# Converter.net
KiCad netlist of a schematic drawn in Altium Designer
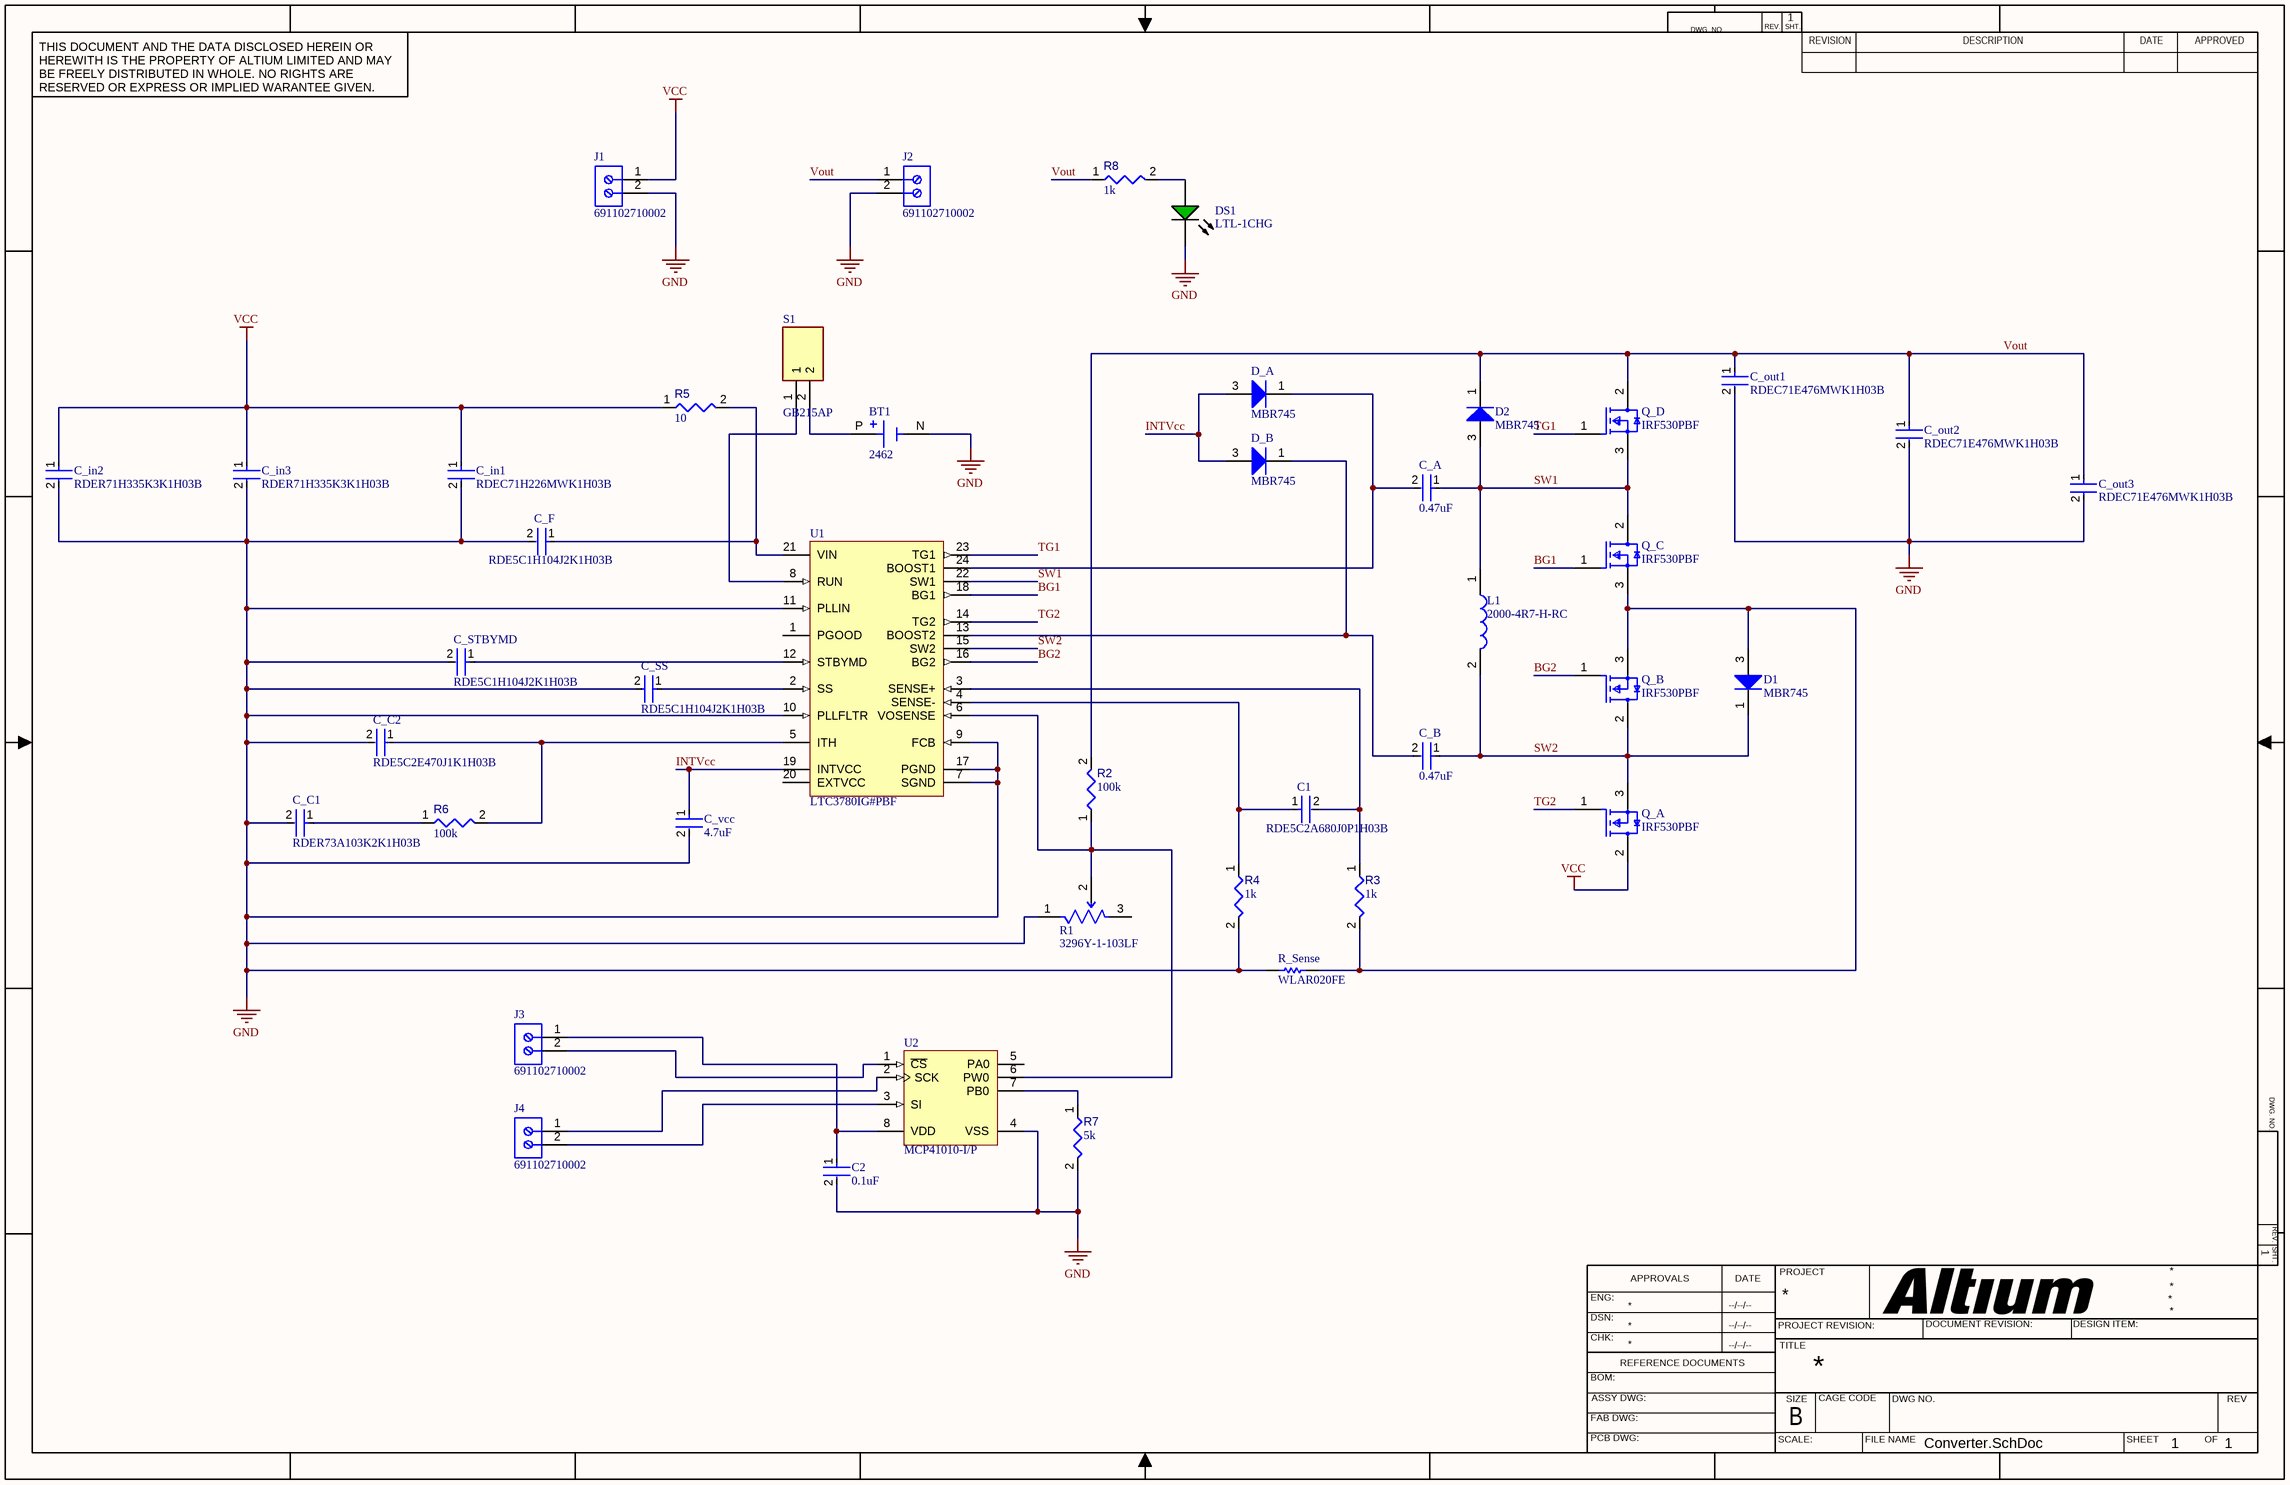
[diagram p0:  Converter.SchDoc]

(export (version "E")
  (design (tool "Eeschema 10.0.6"))
  (components
    (comp (ref "BT1")
      (value "2462")
      (footprint "2462:BAT_2462")
      (description "Battery Holder (Open) AA 2 Cell PC Pin")
      (fields (field (name "MF") "{'manufacturer': u'Keystone'}"))
      (libsource (lib "*") (part "2462"))
    )
    (comp (ref "C1")
      (value "RDE5C2A680J0P1H03B")
      (footprint "FP-RDE0P1-MFG")
      (description "Ceramic Capacitor 68pF ±5% 100V C0G Radial")
      (fields (field (name "TOLERANCE") "5%"))
      (libsource (lib "Altium Content Vault") (part "b4654b650e69147ec39a6b967a45e02"))
    )
    (comp (ref "C2")
      (value "0.1uF")
      (footprint "FP-RDE2M1-MFG")
      (description "Ceramic Capacitor 4.7uF ±10% 50V X7S Radial")
      (fields (field (name "TOLERANCE") "10%"))
      (libsource (lib "Altium Content Vault") (part "b4654b650e69147ec39a6b967a45e02"))
    )
    (comp (ref "C_A")
      (value "0.47uF")
      (footprint "FP-RCE1A2-MFG")
      (description "Cap Ceramic 470nF 50V X7R ±10% Radial 2.5mm +125°C Automotive Bulk")
      (fields (field (name "TOLERANCE") "10%"))
      (libsource (lib "Altium Content Vault") (part "02cd4be3c70576c341d710602a673aa"))
    )
    (comp (ref "C_B")
      (value "0.47uF")
      (footprint "FP-RCE1A2-MFG")
      (description "Cap Ceramic 470nF 50V X7R ±10% Radial 2.5mm +125°C Automotive Bulk")
      (fields (field (name "TOLERANCE") "10%"))
      (libsource (lib "Altium Content Vault") (part "02cd4be3c70576c341d710602a673aa"))
    )
    (comp (ref "C_C1")
      (value "RDER73A103K2K1H03B")
      (footprint "FP-RDE2M1-MFG")
      (description "Ceramic Capacitor 10nF ±10% 1kV X7R Radial")
      (fields (field (name "TOLERANCE") "10%"))
      (libsource (lib "Altium Content Vault") (part "b4654b650e69147ec39a6b967a45e02"))
    )
    (comp (ref "C_C2")
      (value "RDE5C2E470J1K1H03B")
      (footprint "FP-RDE1K1-MFG")
      (description "Ceramic Capacitor 47pF ±5% 250V C0G Radial")
      (libsource (lib "Altium Content Vault") (part "02cd4be3c70576c341d710602a673aa"))
    )
    (comp (ref "C_F")
      (value "RDE5C1H104J2K1H03B")
      (footprint "FP-RDE2M1-MFG")
      (description "Ceramic Capacitor 100nF ±5% 50V C0G Radial")
      (libsource (lib "Altium Content Vault") (part "b4654b650e69147ec39a6b967a45e02"))
    )
    (comp (ref "C_in1")
      (value "RDEC71H226MWK1H03B")
      (footprint "FP-RDEWK1-MFG")
      (description "CAP CER 22UF 50V X7S RADIAL")
      (fields (field (name "TOLERANCE") "20%"))
      (libsource (lib "Altium Content Vault") (part "02cd4be3c70576c341d710602a673aa"))
    )
    (comp (ref "C_in2")
      (value "RDER71H335K3K1H03B")
      (footprint "FP-RDE3M1-MFG")
      (description "Ceramic Capacitor 3.3uF ±10% 50V X7R Radial")
      (fields (field (name "TOLERANCE") "10%"))
      (libsource (lib "Altium Content Vault") (part "b4654b650e69147ec39a6b967a45e02"))
    )
    (comp (ref "C_in3")
      (value "RDER71H335K3K1H03B")
      (footprint "FP-RDE3M1-MFG")
      (description "Ceramic Capacitor 3.3uF ±10% 50V X7R Radial")
      (fields (field (name "TOLERANCE") "10%"))
      (libsource (lib "Altium Content Vault") (part "b4654b650e69147ec39a6b967a45e02"))
    )
    (comp (ref "C_out1")
      (value "RDEC71E476MWK1H03B")
      (footprint "FP-RDEWK1-MFG")
      (description "Ceramic Capacitor 47uF ±20% 25V X7S Radial")
      (fields (field (name "TOLERANCE") "20%"))
      (libsource (lib "Altium Content Vault") (part "02cd4be3c70576c341d710602a673aa"))
    )
    (comp (ref "C_out2")
      (value "RDEC71E476MWK1H03B")
      (footprint "FP-RDEWK1-MFG")
      (description "Ceramic Capacitor 47uF ±20% 25V X7S Radial")
      (fields (field (name "TOLERANCE") "20%"))
      (libsource (lib "Altium Content Vault") (part "02cd4be3c70576c341d710602a673aa"))
    )
    (comp (ref "C_out3")
      (value "RDEC71E476MWK1H03B")
      (footprint "FP-RDEWK1-MFG")
      (description "Ceramic Capacitor 47uF ±20% 25V X7S Radial")
      (fields (field (name "TOLERANCE") "20%"))
      (libsource (lib "Altium Content Vault") (part "02cd4be3c70576c341d710602a673aa"))
    )
    (comp (ref "C_SS")
      (value "RDE5C1H104J2K1H03B")
      (footprint "FP-RDE2M1-MFG")
      (description "Ceramic Capacitor 100nF ±5% 50V C0G Radial")
      (libsource (lib "Altium Content Vault") (part "b4654b650e69147ec39a6b967a45e02"))
    )
    (comp (ref "C_STBYMD")
      (value "RDE5C1H104J2K1H03B")
      (footprint "FP-RDE2M1-MFG")
      (description "Ceramic Capacitor 100nF ±5% 50V C0G Radial")
      (libsource (lib "Altium Content Vault") (part "b4654b650e69147ec39a6b967a45e02"))
    )
    (comp (ref "C_vcc")
      (value "4.7uF")
      (footprint "FP-RDE2M1-MFG")
      (description "Ceramic Capacitor 4.7uF ±10% 50V X7S Radial")
      (fields (field (name "TOLERANCE") "10%"))
      (libsource (lib "Altium Content Vault") (part "b4654b650e69147ec39a6b967a45e02"))
    )
    (comp (ref "D1")
      (value "MBR745")
      (footprint "ONSC-TO-220-2-221B-04_E")
      (description "SWITCHMODE(TM) Power Rectifier, 2-Pin TO-220, Tube")
      (fields (field (name "MANUFACTURER") "On Semiconductor"))
      (libsource (lib "Altium Content Vault") (part "ONSC-D-K1A3-2_A"))
    )
    (comp (ref "D2")
      (value "MBR745")
      (footprint "ONSC-TO-220-2-221B-04_E")
      (description "SWITCHMODE(TM) Power Rectifier, 2-Pin TO-220, Tube")
      (fields (field (name "MANUFACTURER") "On Semiconductor"))
      (libsource (lib "Altium Content Vault") (part "ONSC-D-K1A3-2_A"))
    )
    (comp (ref "DS1")
      (value "LTL-1CHG")
      (footprint "LTST-LTL-1CHG-2")
      (description "LED Uni-Color Green, 100 mW, 30 mA, -55 to 100 degC, 2-Pin THD, RoHS, Bulk")
      (fields (field (name "POWER") "100mW") (field (name "MANUFACTURER") "Lite-On"))
      (libsource (lib "Colton's Workspace") (part "LED-GREEN-AK-2"))
    )
    (comp (ref "D_A")
      (value "MBR745")
      (footprint "ONSC-TO-220-2-221B-04_E")
      (description "SWITCHMODE(TM) Power Rectifier, 2-Pin TO-220, Tube")
      (fields (field (name "MANUFACTURER") "On Semiconductor"))
      (libsource (lib "Altium Content Vault") (part "ONSC-D-K1A3-2_A"))
    )
    (comp (ref "D_B")
      (value "MBR745")
      (footprint "ONSC-TO-220-2-221B-04_E")
      (description "SWITCHMODE(TM) Power Rectifier, 2-Pin TO-220, Tube")
      (fields (field (name "MANUFACTURER") "On Semiconductor"))
      (libsource (lib "Altium Content Vault") (part "ONSC-D-K1A3-2_A"))
    )
    (comp (ref "J1")
      (value "691102710002")
      (footprint "691102710002")
      (description "Series 102 - 5.00 mm Horizontal Entry Modular with Pressure Clamp WR-TBL, 2 pin")
      (fields (field (name "MANUFACTURER") "Wurth Elektronik") (field (name "PUBLISHER") "WurthElektronik"))
      (libsource (lib "Altium Content Vault") (part "WE-CN-1P-F-TB2"))
    )
    (comp (ref "J2")
      (value "691102710002")
      (footprint "691102710002")
      (description "Series 102 - 5.00 mm Horizontal Entry Modular with Pressure Clamp WR-TBL, 2 pin")
      (fields (field (name "MANUFACTURER") "Wurth Elektronik") (field (name "PUBLISHER") "WurthElektronik"))
      (libsource (lib "Altium Content Vault") (part "WE-CN-1P-F-TB2"))
    )
    (comp (ref "J3")
      (value "691102710002")
      (footprint "691102710002")
      (description "Series 102 - 5.00 mm Horizontal Entry Modular with Pressure Clamp WR-TBL, 2 pin")
      (fields (field (name "MANUFACTURER") "Wurth Elektronik") (field (name "PUBLISHER") "WurthElektronik"))
      (libsource (lib "Altium Content Vault") (part "WE-CN-1P-F-TB2"))
    )
    (comp (ref "J4")
      (value "691102710002")
      (footprint "691102710002")
      (description "Series 102 - 5.00 mm Horizontal Entry Modular with Pressure Clamp WR-TBL, 2 pin")
      (fields (field (name "MANUFACTURER") "Wurth Elektronik") (field (name "PUBLISHER") "WurthElektronik"))
      (libsource (lib "Altium Content Vault") (part "WE-CN-1P-F-TB2"))
    )
    (comp (ref "L1")
      (value "2000-4R7-H-RC")
      (footprint "SamacSys:20004R7HRC")
      (description "Inductor")
      (libsource (lib "*") (part "2000-4R7-H-RC"))
    )
    (comp (ref "Q_A")
      (value "IRF530PBF")
      (footprint "FP-X15-0364-MFG")
      (description "MOSFET N-CH 100V 14A TO-220AB")
      (fields
        (field (name "MANUFACTURER") "Vishay")
        (field (name "OCTOPART") "https://octopart.com/irf530pbf-vishay-46547999")
      )
      (libsource (lib "Altium Content Vault") (part "277670f45256a45703965f138927d09"))
    )
    (comp (ref "Q_B")
      (value "IRF530PBF")
      (footprint "FP-X15-0364-MFG")
      (description "MOSFET N-CH 100V 14A TO-220AB")
      (fields
        (field (name "MANUFACTURER") "Vishay")
        (field (name "OCTOPART") "https://octopart.com/irf530pbf-vishay-46547999")
      )
      (libsource (lib "Altium Content Vault") (part "277670f45256a45703965f138927d09"))
    )
    (comp (ref "Q_C")
      (value "IRF530PBF")
      (footprint "FP-X15-0364-MFG")
      (description "MOSFET N-CH 100V 14A TO-220AB")
      (fields
        (field (name "MANUFACTURER") "Vishay")
        (field (name "OCTOPART") "https://octopart.com/irf530pbf-vishay-46547999")
      )
      (libsource (lib "Altium Content Vault") (part "277670f45256a45703965f138927d09"))
    )
    (comp (ref "Q_D")
      (value "IRF530PBF")
      (footprint "FP-X15-0364-MFG")
      (description "MOSFET N-CH 100V 14A TO-220AB")
      (fields
        (field (name "MANUFACTURER") "Vishay")
        (field (name "OCTOPART") "https://octopart.com/irf530pbf-vishay-46547999")
      )
      (libsource (lib "Altium Content Vault") (part "277670f45256a45703965f138927d09"))
    )
    (comp (ref "R1")
      (value "3296Y-1-103LF")
      (footprint "FP-3296Y-MFG")
      (description "TRIMMER 10K OHM 0.5W PC PIN TOP")
      (fields (field (name "TOLERANCE") "10%"))
      (libsource (lib "Altium Content Vault") (part "2dcfd2547301a7d3209a5e99acfd772"))
    )
    (comp (ref "R2")
      (value "100k")
      (footprint "RESA60-630X240")
      (description "Axial Resistor, 1 KOhm, +/- 1%, 250 mW, -55 to 155 degC, 2-Pin THD, RoHS, Bulk")
      (fields (field (name "TOLERANCE") "1%") (field (name "POWER") "250mW"))
      (libsource (lib "Colton's Workspace") (part "RES-2"))
    )
    (comp (ref "R3")
      (value "1k")
      (footprint "RESA60-630X240")
      (description "Axial Resistor, 1 KOhm, +/- 1%, 250 mW, -55 to 155 degC, 2-Pin THD, RoHS, Bulk")
      (fields (field (name "TOLERANCE") "1%") (field (name "POWER") "250mW"))
      (libsource (lib "Colton's Workspace") (part "RES-2"))
    )
    (comp (ref "R4")
      (value "1k")
      (footprint "RESA60-630X240")
      (description "Axial Resistor, 1 KOhm, +/- 1%, 250 mW, -55 to 155 degC, 2-Pin THD, RoHS, Bulk")
      (fields (field (name "TOLERANCE") "1%") (field (name "POWER") "250mW"))
      (libsource (lib "Colton's Workspace") (part "RES-2"))
    )
    (comp (ref "R5")
      (value "10")
      (footprint "RESA60-630X240")
      (description "Axial Resistor, 1 KOhm, +/- 1%, 250 mW, -55 to 155 degC, 2-Pin THD, RoHS, Bulk")
      (fields (field (name "TOLERANCE") "1%") (field (name "POWER") "250mW"))
      (libsource (lib "Colton's Workspace") (part "RES-2"))
    )
    (comp (ref "R6")
      (value "100k")
      (footprint "RESA60-630X240")
      (description "Axial Resistor, 1 KOhm, +/- 1%, 250 mW, -55 to 155 degC, 2-Pin THD, RoHS, Bulk")
      (fields (field (name "TOLERANCE") "1%") (field (name "POWER") "250mW"))
      (libsource (lib "Colton's Workspace") (part "RES-2"))
    )
    (comp (ref "R7")
      (value "5k")
      (footprint "RESA60-630X240")
      (description "Axial Resistor, 1 KOhm, +/- 1%, 250 mW, -55 to 155 degC, 2-Pin THD, RoHS, Bulk")
      (fields (field (name "TOLERANCE") "1%") (field (name "POWER") "250mW"))
      (libsource (lib "Colton's Workspace") (part "RES-2"))
    )
    (comp (ref "R8")
      (value "1k")
      (footprint "RESA60-630X240")
      (description "Axial Resistor, 1 KOhm, +/- 1%, 250 mW, -55 to 155 degC, 2-Pin THD, RoHS, Bulk")
      (fields (field (name "TOLERANCE") "1%") (field (name "POWER") "250mW"))
      (libsource (lib "Colton's Workspace") (part "RES-2"))
    )
    (comp (ref "R_Sense")
      (value "WLAR020FE")
      (footprint "OMTE-WLA-2_V2")
      (description "Miniature Wirewound Current Sense, 0.02 Ohm +/-1%, 0.5 W, 2-Pin THD, RoHS, 25pc Pack")
      (fields (field (name "MANUFACTURER") "Ohmite"))
      (libsource (lib "Altium Content Vault") (part "OMTE-RES-2"))
    )
    (comp (ref "S1")
      (value "GB215AP")
      (footprint "SamacSys:GB215AP")
      (description "Switch")
      (libsource (lib "*") (part "GB215AP"))
    )
    (comp (ref "U1")
      (value "LTC3780IG#PBF")
      (footprint "LT-G-24_M")
      (fields (field (name "MANUFACTURER") "Linear Technology"))
      (libsource (lib "Altium Content Vault") (part "LT-LTC3780-G-24"))
    )
    (comp (ref "U2")
      (value "MCP41010-I/P")
      (footprint "PDIP300-P8")
      (description "Single/Dual Digital Potentiometer with SPI Interface, 8-Pin PDIP, Industrial Temperature")
      (libsource (lib "Altium Content Vault") (part "IN-DPOT-MCP41XXX-8"))
    )
  )
  (nets
    (net (code "1") (name "/BG1") (class "Default")
      (node (ref "Q_C") (pin "1") (pinfunction "G_1") (pintype "passive"))
      (node (ref "U1") (pin "18") (pinfunction "BG1_18") (pintype "output"))
    )
    (net (code "2") (name "/BG2") (class "Default")
      (node (ref "Q_B") (pin "1") (pinfunction "G_1") (pintype "passive"))
      (node (ref "U1") (pin "16") (pinfunction "BG2_16") (pintype "output"))
    )
    (net (code "3") (name "/INTVcc") (class "Default")
      (node (ref "C_vcc") (pin "1") (pinfunction "1_1") (pintype "passive"))
      (node (ref "D_A") (pin "3") (pinfunction "A_3") (pintype "passive"))
      (node (ref "D_B") (pin "3") (pinfunction "A_3") (pintype "passive"))
      (node (ref "U1") (pin "19") (pinfunction "INTVCC_19") (pintype "power_in"))
    )
    (net (code "4") (name "/SW1") (class "Default")
      (node (ref "C_A") (pin "1") (pinfunction "1_1") (pintype "passive"))
      (node (ref "D2") (pin "3") (pinfunction "A_3") (pintype "passive"))
      (node (ref "L1") (pin "1") (pinfunction "1_1") (pintype "passive"))
      (node (ref "Q_C") (pin "2") (pinfunction "D_2") (pintype "passive"))
      (node (ref "Q_D") (pin "3") (pinfunction "S_3") (pintype "passive"))
      (node (ref "U1") (pin "22") (pinfunction "SW1_22") (pintype "passive"))
    )
    (net (code "5") (name "/SW2") (class "Default")
      (node (ref "C_B") (pin "1") (pinfunction "1_1") (pintype "passive"))
      (node (ref "D1") (pin "1") (pinfunction "K_1") (pintype "passive"))
      (node (ref "L1") (pin "2") (pinfunction "2_2") (pintype "passive"))
      (node (ref "Q_A") (pin "3") (pinfunction "S_3") (pintype "passive"))
      (node (ref "Q_B") (pin "2") (pinfunction "D_2") (pintype "passive"))
      (node (ref "U1") (pin "15") (pinfunction "SW2_15") (pintype "passive"))
    )
    (net (code "6") (name "/TG1") (class "Default")
      (node (ref "Q_D") (pin "1") (pinfunction "G_1") (pintype "passive"))
      (node (ref "U1") (pin "23") (pinfunction "TG1_23") (pintype "output"))
    )
    (net (code "7") (name "/TG2") (class "Default")
      (node (ref "Q_A") (pin "1") (pinfunction "G_1") (pintype "passive"))
      (node (ref "U1") (pin "14") (pinfunction "TG2_14") (pintype "output"))
    )
    (net (code "8") (name "/Vout") (class "Default")
      (node (ref "C_out1") (pin "1") (pinfunction "1_1") (pintype "passive"))
      (node (ref "C_out2") (pin "1") (pinfunction "1_1") (pintype "passive"))
      (node (ref "C_out3") (pin "1") (pinfunction "1_1") (pintype "passive"))
      (node (ref "D2") (pin "1") (pinfunction "K_1") (pintype "passive"))
      (node (ref "J2") (pin "1") (pinfunction "1_1") (pintype "passive"))
      (node (ref "Q_D") (pin "2") (pinfunction "D_2") (pintype "passive"))
      (node (ref "R2") (pin "2") (pinfunction "2_2") (pintype "passive"))
      (node (ref "R8") (pin "1") (pinfunction "1_1") (pintype "passive"))
    )
    (net (code "9") (name "GND") (class "Default")
      (node (ref "BT1") (pin "N") (pinfunction "NEG_N") (pintype "passive"))
      (node (ref "C2") (pin "2") (pinfunction "2_2") (pintype "passive"))
      (node (ref "C_C1") (pin "2") (pinfunction "2_2") (pintype "passive"))
      (node (ref "C_C2") (pin "2") (pinfunction "2_2") (pintype "passive"))
      (node (ref "C_F") (pin "2") (pinfunction "2_2") (pintype "passive"))
      (node (ref "C_SS") (pin "2") (pinfunction "2_2") (pintype "passive"))
      (node (ref "C_STBYMD") (pin "2") (pinfunction "2_2") (pintype "passive"))
      (node (ref "C_in1") (pin "2") (pinfunction "2_2") (pintype "passive"))
      (node (ref "C_in2") (pin "2") (pinfunction "2_2") (pintype "passive"))
      (node (ref "C_in3") (pin "2") (pinfunction "2_2") (pintype "passive"))
      (node (ref "C_out1") (pin "2") (pinfunction "2_2") (pintype "passive"))
      (node (ref "C_out2") (pin "2") (pinfunction "2_2") (pintype "passive"))
      (node (ref "C_out3") (pin "2") (pinfunction "2_2") (pintype "passive"))
      (node (ref "C_vcc") (pin "2") (pinfunction "2_2") (pintype "passive"))
      (node (ref "DS1") (pin "2") (pinfunction "K_2") (pintype "passive"))
      (node (ref "J1") (pin "2") (pinfunction "2_2") (pintype "passive"))
      (node (ref "J2") (pin "2") (pinfunction "2_2") (pintype "passive"))
      (node (ref "R1") (pin "1") (pinfunction "CCW_1") (pintype "passive"))
      (node (ref "R4") (pin "2") (pinfunction "2_2") (pintype "passive"))
      (node (ref "R7") (pin "2") (pinfunction "2_2") (pintype "passive"))
      (node (ref "R_Sense") (pin "1") (pinfunction "1_1") (pintype "passive"))
      (node (ref "U1") (pin "10") (pinfunction "PLLFLTR_10") (pintype "input"))
      (node (ref "U1") (pin "11") (pinfunction "PLLIN_11") (pintype "input"))
      (node (ref "U1") (pin "17") (pinfunction "PGND_17") (pintype "power_in"))
      (node (ref "U1") (pin "7") (pinfunction "SGND_7") (pintype "power_in"))
      (node (ref "U1") (pin "9") (pinfunction "FCB_9") (pintype "input"))
      (node (ref "U2") (pin "4") (pinfunction "VSS_4") (pintype "power_in"))
    )
    (net (code "10") (name "Net-(BT1-POS)") (class "Default")
      (node (ref "BT1") (pin "P") (pinfunction "POS_P") (pintype "passive"))
      (node (ref "S1") (pin "2") (pinfunction "2_2") (pintype "passive"))
    )
    (net (code "11") (name "Net-(C_C1-Pad1)") (class "Default")
      (node (ref "C_C1") (pin "1") (pinfunction "1_1") (pintype "passive"))
      (node (ref "R6") (pin "1") (pinfunction "1_1") (pintype "passive"))
    )
    (net (code "12") (name "Net-(D1-A)") (class "Default")
      (node (ref "D1") (pin "3") (pinfunction "A_3") (pintype "passive"))
      (node (ref "Q_B") (pin "3") (pinfunction "S_3") (pintype "passive"))
      (node (ref "Q_C") (pin "3") (pinfunction "S_3") (pintype "passive"))
      (node (ref "R3") (pin "2") (pinfunction "2_2") (pintype "passive"))
      (node (ref "R_Sense") (pin "2") (pinfunction "2_2") (pintype "passive"))
    )
    (net (code "13") (name "Net-(DS1-A)") (class "Default")
      (node (ref "DS1") (pin "1") (pinfunction "A_1") (pintype "passive"))
      (node (ref "R8") (pin "2") (pinfunction "2_2") (pintype "passive"))
    )
    (net (code "14") (name "Net-(D_A-K)") (class "Default")
      (node (ref "C_A") (pin "2") (pinfunction "2_2") (pintype "passive"))
      (node (ref "D_A") (pin "1") (pinfunction "K_1") (pintype "passive"))
      (node (ref "U1") (pin "24") (pinfunction "BOOST1_24") (pintype "passive"))
    )
    (net (code "15") (name "Net-(D_B-K)") (class "Default")
      (node (ref "C_B") (pin "2") (pinfunction "2_2") (pintype "passive"))
      (node (ref "D_B") (pin "1") (pinfunction "K_1") (pintype "passive"))
      (node (ref "U1") (pin "13") (pinfunction "BOOST2_13") (pintype "passive"))
    )
    (net (code "16") (name "Net-(R1-WIPER)") (class "Default")
      (node (ref "R1") (pin "2") (pinfunction "WIPER_2") (pintype "passive"))
      (node (ref "R2") (pin "1") (pinfunction "1_1") (pintype "passive"))
      (node (ref "U1") (pin "6") (pinfunction "VOSENSE_6") (pintype "input"))
      (node (ref "U2") (pin "6") (pinfunction "PW0_6") (pintype "passive"))
    )
    (net (code "17") (name "Net-(U1-ITH)") (class "Default")
      (node (ref "C_C2") (pin "1") (pinfunction "1_1") (pintype "passive"))
      (node (ref "R6") (pin "2") (pinfunction "2_2") (pintype "passive"))
      (node (ref "U1") (pin "5") (pinfunction "ITH_5") (pintype "passive"))
    )
    (net (code "18") (name "Net-(U1-RUN)") (class "Default")
      (node (ref "S1") (pin "1") (pinfunction "1_1") (pintype "passive"))
      (node (ref "U1") (pin "8") (pinfunction "RUN_8") (pintype "input"))
    )
    (net (code "19") (name "Net-(U1-SENSE+)") (class "Default")
      (node (ref "C1") (pin "2") (pinfunction "2_2") (pintype "passive"))
      (node (ref "R3") (pin "1") (pinfunction "1_1") (pintype "passive"))
      (node (ref "U1") (pin "3") (pinfunction "SENSE+_3") (pintype "input"))
    )
    (net (code "20") (name "Net-(U1-SENSE-)") (class "Default")
      (node (ref "C1") (pin "1") (pinfunction "1_1") (pintype "passive"))
      (node (ref "R4") (pin "1") (pinfunction "1_1") (pintype "passive"))
      (node (ref "U1") (pin "4") (pinfunction "SENSE-_4") (pintype "input"))
    )
    (net (code "21") (name "Net-(U1-SS)") (class "Default")
      (node (ref "C_SS") (pin "1") (pinfunction "1_1") (pintype "passive"))
      (node (ref "U1") (pin "2") (pinfunction "SS_2") (pintype "input"))
    )
    (net (code "22") (name "Net-(U1-STBYMD)") (class "Default")
      (node (ref "C_STBYMD") (pin "1") (pinfunction "1_1") (pintype "passive"))
      (node (ref "U1") (pin "12") (pinfunction "STBYMD_12") (pintype "input"))
    )
    (net (code "23") (name "Net-(U1-VIN)") (class "Default")
      (node (ref "C_F") (pin "1") (pinfunction "1_1") (pintype "passive"))
      (node (ref "R5") (pin "2") (pinfunction "2_2") (pintype "passive"))
      (node (ref "U1") (pin "21") (pinfunction "VIN_21") (pintype "power_in"))
    )
    (net (code "24") (name "Net-(U2-PB0)") (class "Default")
      (node (ref "R7") (pin "1") (pinfunction "1_1") (pintype "passive"))
      (node (ref "U2") (pin "7") (pinfunction "PB0_7") (pintype "passive"))
    )
    (net (code "25") (name "Net-(U2-SCK)") (class "Default")
      (node (ref "J4") (pin "1") (pinfunction "1_1") (pintype "passive"))
      (node (ref "U2") (pin "2") (pinfunction "SCK_2") (pintype "input"))
    )
    (net (code "26") (name "Net-(U2-SI)") (class "Default")
      (node (ref "J4") (pin "2") (pinfunction "2_2") (pintype "passive"))
      (node (ref "U2") (pin "3") (pinfunction "SI_3") (pintype "input"))
    )
    (net (code "27") (name "Net-(U2-VDD)") (class "Default")
      (node (ref "C2") (pin "1") (pinfunction "1_1") (pintype "passive"))
      (node (ref "J3") (pin "1") (pinfunction "1_1") (pintype "passive"))
      (node (ref "U2") (pin "8") (pinfunction "VDD_8") (pintype "power_in"))
    )
    (net (code "28") (name "Net-(U2-~{CS})") (class "Default")
      (node (ref "J3") (pin "2") (pinfunction "2_2") (pintype "passive"))
      (node (ref "U2") (pin "1") (pinfunction "~{CS}_1") (pintype "input"))
    )
    (net (code "29") (name "VCC") (class "Default")
      (node (ref "C_in1") (pin "1") (pinfunction "1_1") (pintype "passive"))
      (node (ref "C_in2") (pin "1") (pinfunction "1_1") (pintype "passive"))
      (node (ref "C_in3") (pin "1") (pinfunction "1_1") (pintype "passive"))
      (node (ref "J1") (pin "1") (pinfunction "1_1") (pintype "passive"))
      (node (ref "Q_A") (pin "2") (pinfunction "D_2") (pintype "passive"))
      (node (ref "R5") (pin "1") (pinfunction "1_1") (pintype "passive"))
    )
    (net (code "30") (name "unconnected-(R1-CW-Pad3)") (class "Default")
      (node (ref "R1") (pin "3") (pinfunction "CW_3") (pintype "passive"))
    )
    (net (code "31") (name "unconnected-(U1-EXTVCC-Pad20)") (class "Default")
      (node (ref "U1") (pin "20") (pinfunction "EXTVCC_20") (pintype "power_in"))
    )
    (net (code "32") (name "unconnected-(U1-PGOOD-Pad1)") (class "Default")
      (node (ref "U1") (pin "1") (pinfunction "PGOOD_1") (pintype "open_collector"))
    )
    (net (code "33") (name "unconnected-(U2-PA0-Pad5)") (class "Default")
      (node (ref "U2") (pin "5") (pinfunction "PA0_5") (pintype "passive"))
    )
  )
)
